# Power_MPU.net
KiCad netlist of a schematic drawn in Altium Designer
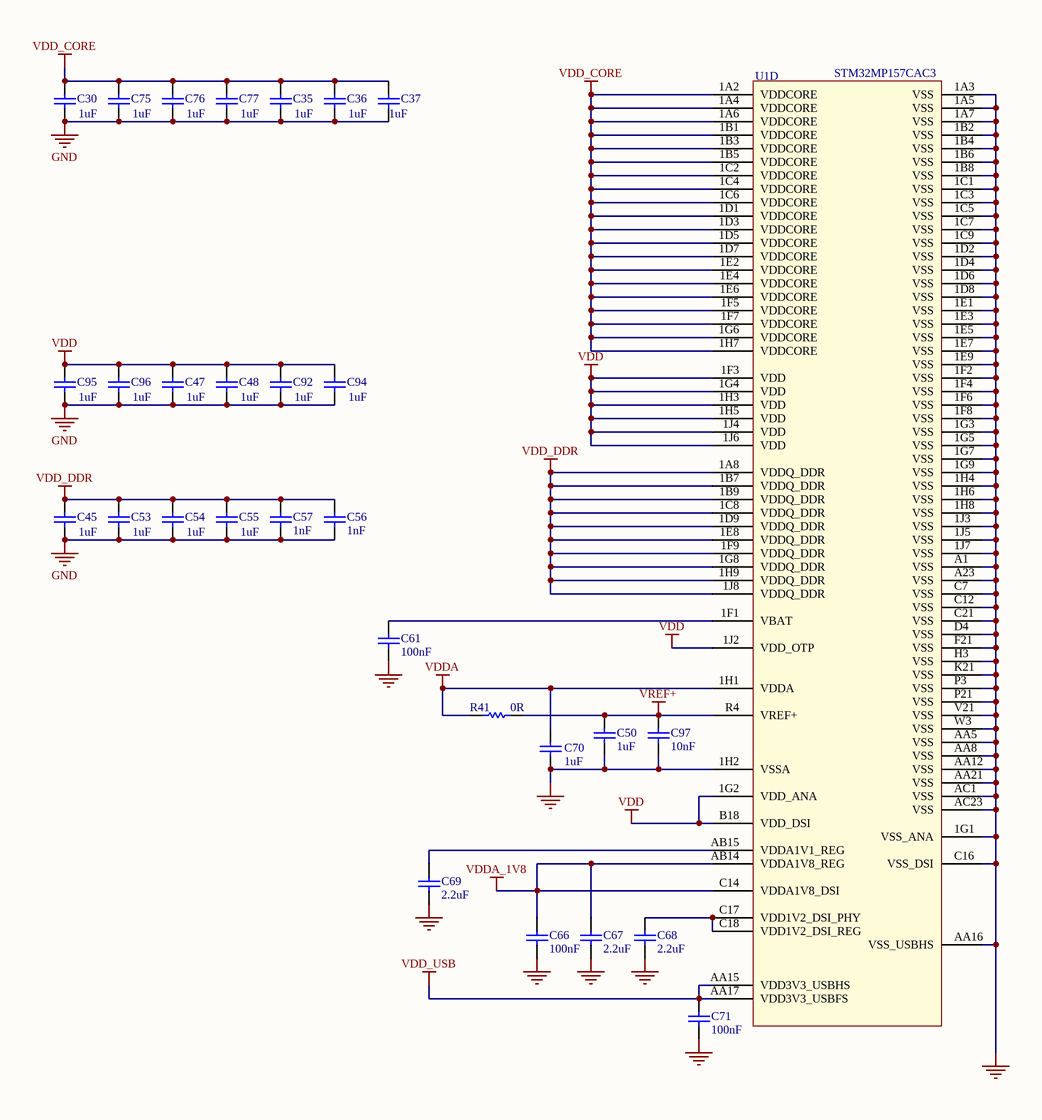
[diagram p0: Power_MPU.SchDoc]

(export (version "E")
  (design (tool "Eeschema 10.0.6"))
  (components
    (comp (ref "C30")
      (value "1uF")
      (footprint "C0402")
      (description "Capacitor, MLCC, 1uF, 25V, X5R, 10%, 0402, T=0,5mm")
      (fields
        (field (name "INTERNAL_PART_NUMBER") "MCD-00095")
        (field (name "MANUFACTURER_PART_NUMBER") "GRM155R61E105KA12")
        (field (name "PROVIDED_BY") "SUBCO")
      )
      (libsource (lib "MCD_PARTS_database") (part "Capacitor"))
    )
    (comp (ref "C35")
      (value "1uF")
      (footprint "C0402")
      (description "Capacitor, MLCC, 1uF, 25V, X5R, 10%, 0402, T=0,5mm")
      (fields
        (field (name "INTERNAL_PART_NUMBER") "MCD-00095")
        (field (name "MANUFACTURER_PART_NUMBER") "GRM155R61E105KA12")
        (field (name "PROVIDED_BY") "SUBCO")
      )
      (libsource (lib "MCD_PARTS_database") (part "Capacitor"))
    )
    (comp (ref "C36")
      (value "1uF")
      (footprint "C0402")
      (description "Capacitor, MLCC, 1uF, 25V, X5R, 10%, 0402, T=0,5mm")
      (fields
        (field (name "INTERNAL_PART_NUMBER") "MCD-00095")
        (field (name "MANUFACTURER_PART_NUMBER") "GRM155R61E105KA12")
        (field (name "PROVIDED_BY") "SUBCO")
      )
      (libsource (lib "MCD_PARTS_database") (part "Capacitor"))
    )
    (comp (ref "C37")
      (value "1uF")
      (footprint "C0402")
      (description "Capacitor, MLCC, 1uF, 25V, X5R, 10%, 0402, T=0,5mm")
      (fields
        (field (name "INTERNAL_PART_NUMBER") "MCD-00095")
        (field (name "MANUFACTURER_PART_NUMBER") "GRM155R61E105KA12")
        (field (name "PROVIDED_BY") "SUBCO")
      )
      (libsource (lib "MCD_PARTS_database") (part "Capacitor"))
    )
    (comp (ref "C45")
      (value "1uF")
      (footprint "C0402")
      (description "Capacitor, MLCC, 1uF, 25V, X5R, 10%, 0402, T=0,5mm")
      (fields
        (field (name "INTERNAL_PART_NUMBER") "MCD-00095")
        (field (name "MANUFACTURER_PART_NUMBER") "GRM155R61E105KA12")
        (field (name "PROVIDED_BY") "SUBCO")
      )
      (libsource (lib "MCD_PARTS_database") (part "Capacitor"))
    )
    (comp (ref "C47")
      (value "1uF")
      (footprint "C0402")
      (description "Capacitor, MLCC, 1uF, 25V, X5R, 10%, 0402, T=0,5mm")
      (fields
        (field (name "INTERNAL_PART_NUMBER") "MCD-00095")
        (field (name "MANUFACTURER_PART_NUMBER") "GRM155R61E105KA12")
        (field (name "PROVIDED_BY") "SUBCO")
      )
      (libsource (lib "MCD_PARTS_database") (part "Capacitor"))
    )
    (comp (ref "C48")
      (value "1uF")
      (footprint "C0402")
      (description "Capacitor, MLCC, 1uF, 25V, X5R, 10%, 0402, T=0,5mm")
      (fields
        (field (name "INTERNAL_PART_NUMBER") "MCD-00095")
        (field (name "MANUFACTURER_PART_NUMBER") "GRM155R61E105KA12")
        (field (name "PROVIDED_BY") "SUBCO")
      )
      (libsource (lib "MCD_PARTS_database") (part "Capacitor"))
    )
    (comp (ref "C50")
      (value "1uF")
      (footprint "C0402")
      (description "Capacitor, MLCC, 1uF, 25V, X5R, 10%, 0402, T=0,5mm")
      (fields
        (field (name "INTERNAL_PART_NUMBER") "MCD-00095")
        (field (name "MANUFACTURER_PART_NUMBER") "GRM155R61E105KA12")
        (field (name "PROVIDED_BY") "SUBCO")
      )
      (libsource (lib "MCD_PARTS_database") (part "Capacitor"))
    )
    (comp (ref "C53")
      (value "1uF")
      (footprint "C0402")
      (description "Capacitor, MLCC, 1uF, 25V, X5R, 10%, 0402, T=0,5mm")
      (fields
        (field (name "INTERNAL_PART_NUMBER") "MCD-00095")
        (field (name "MANUFACTURER_PART_NUMBER") "GRM155R61E105KA12")
        (field (name "PROVIDED_BY") "SUBCO")
      )
      (libsource (lib "MCD_PARTS_database") (part "Capacitor"))
    )
    (comp (ref "C54")
      (value "1uF")
      (footprint "C0402")
      (description "Capacitor, MLCC, 1uF, 25V, X5R, 10%, 0402, T=0,5mm")
      (fields
        (field (name "INTERNAL_PART_NUMBER") "MCD-00095")
        (field (name "MANUFACTURER_PART_NUMBER") "GRM155R61E105KA12")
        (field (name "PROVIDED_BY") "SUBCO")
      )
      (libsource (lib "MCD_PARTS_database") (part "Capacitor"))
    )
    (comp (ref "C55")
      (value "1uF")
      (footprint "C0402")
      (description "Capacitor, MLCC, 1uF, 25V, X5R, 10%, 0402, T=0,5mm")
      (fields
        (field (name "INTERNAL_PART_NUMBER") "MCD-00095")
        (field (name "MANUFACTURER_PART_NUMBER") "GRM155R61E105KA12")
        (field (name "PROVIDED_BY") "SUBCO")
      )
      (libsource (lib "MCD_PARTS_database") (part "Capacitor"))
    )
    (comp (ref "C56")
      (value "1nF")
      (footprint "C0402")
      (description "Capacitor, MLCC, 1nF, 16V, X7R, 10%, 0402, T=0.5mm")
      (fields
        (field (name "INTERNAL_PART_NUMBER") "MCD-00198")
        (field (name "MANUFACTURER_PART_NUMBER") "CC0402KRX7R7BB102")
        (field (name "PROVIDED_BY") "SUBCO")
      )
      (libsource (lib "MCD_PARTS_database") (part "Capacitor"))
    )
    (comp (ref "C57")
      (value "1nF")
      (footprint "C0402")
      (description "Capacitor, MLCC, 1nF, 16V, X7R, 10%, 0402, T=0.5mm")
      (fields
        (field (name "INTERNAL_PART_NUMBER") "MCD-00198")
        (field (name "MANUFACTURER_PART_NUMBER") "CC0402KRX7R7BB102")
        (field (name "PROVIDED_BY") "SUBCO")
      )
      (libsource (lib "MCD_PARTS_database") (part "Capacitor"))
    )
    (comp (ref "C61")
      (value "100nF")
      (footprint "C0402")
      (description "Capacitor, MLCC, 100nF, 16V, X7R, 10%, 0402, T=0.5mm")
      (fields
        (field (name "INTERNAL_PART_NUMBER") "MCD-00006")
        (field (name "MANUFACTURER_PART_NUMBER") "CC0402KRX7R7BB104")
        (field (name "PROVIDED_BY") "SUBCO")
      )
      (libsource (lib "MCD_PARTS_database") (part "Capacitor"))
    )
    (comp (ref "C66")
      (value "100nF")
      (footprint "C0402")
      (description "Capacitor, MLCC, 100nF, 16V, X7R, 10%, 0402, T=0.5mm")
      (fields
        (field (name "INTERNAL_PART_NUMBER") "MCD-00006")
        (field (name "MANUFACTURER_PART_NUMBER") "CC0402KRX7R7BB104")
        (field (name "PROVIDED_BY") "SUBCO")
      )
      (libsource (lib "MCD_PARTS_database") (part "Capacitor"))
    )
    (comp (ref "C67")
      (value "2.2uF")
      (footprint "C0402")
      (description "Capacitor,MLCC,2.2uF,6V3,X5R,10%,0402,T=0.5")
      (fields
        (field (name "INTERNAL_PART_NUMBER") "MCD-01823")
        (field (name "MANUFACTURER_PART_NUMBER") "GRM155R60J225KE95D")
        (field (name "PROVIDED_BY") "SUBCO")
      )
      (libsource (lib "MCD_PARTS_database") (part "Capacitor"))
    )
    (comp (ref "C68")
      (value "2.2uF")
      (footprint "C0402")
      (description "Capacitor,MLCC,2.2uF,6V3,X5R,10%,0402,T=0.5")
      (fields
        (field (name "INTERNAL_PART_NUMBER") "MCD-01823")
        (field (name "MANUFACTURER_PART_NUMBER") "GRM155R60J225KE95D")
        (field (name "PROVIDED_BY") "SUBCO")
      )
      (libsource (lib "MCD_PARTS_database") (part "Capacitor"))
    )
    (comp (ref "C69")
      (value "2.2uF")
      (footprint "C0402")
      (description "Capacitor,MLCC,2.2uF,6V3,X5R,10%,0402,T=0.5")
      (fields
        (field (name "INTERNAL_PART_NUMBER") "MCD-01823")
        (field (name "MANUFACTURER_PART_NUMBER") "GRM155R60J225KE95D")
        (field (name "PROVIDED_BY") "SUBCO")
      )
      (libsource (lib "MCD_PARTS_database") (part "Capacitor"))
    )
    (comp (ref "C70")
      (value "1uF")
      (footprint "C0402")
      (description "Capacitor, MLCC, 1uF, 25V, X5R, 10%, 0402, T=0,5mm")
      (fields
        (field (name "INTERNAL_PART_NUMBER") "MCD-00095")
        (field (name "MANUFACTURER_PART_NUMBER") "GRM155R61E105KA12")
        (field (name "PROVIDED_BY") "SUBCO")
      )
      (libsource (lib "MCD_PARTS_database") (part "Capacitor"))
    )
    (comp (ref "C71")
      (value "100nF")
      (footprint "C0402")
      (description "Capacitor, MLCC, 100nF, 16V, X7R, 10%, 0402, T=0.5mm")
      (fields
        (field (name "INTERNAL_PART_NUMBER") "MCD-00006")
        (field (name "MANUFACTURER_PART_NUMBER") "CC0402KRX7R7BB104")
        (field (name "PROVIDED_BY") "SUBCO")
      )
      (libsource (lib "MCD_PARTS_database") (part "Capacitor"))
    )
    (comp (ref "C75")
      (value "1uF")
      (footprint "C0402")
      (description "Capacitor, MLCC, 1uF, 25V, X5R, 10%, 0402, T=0,5mm")
      (fields
        (field (name "INTERNAL_PART_NUMBER") "MCD-00095")
        (field (name "MANUFACTURER_PART_NUMBER") "GRM155R61E105KA12")
        (field (name "PROVIDED_BY") "SUBCO")
      )
      (libsource (lib "MCD_PARTS_database") (part "Capacitor"))
    )
    (comp (ref "C76")
      (value "1uF")
      (footprint "C0402")
      (description "Capacitor, MLCC, 1uF, 25V, X5R, 10%, 0402, T=0,5mm")
      (fields
        (field (name "INTERNAL_PART_NUMBER") "MCD-00095")
        (field (name "MANUFACTURER_PART_NUMBER") "GRM155R61E105KA12")
        (field (name "PROVIDED_BY") "SUBCO")
      )
      (libsource (lib "MCD_PARTS_database") (part "Capacitor"))
    )
    (comp (ref "C77")
      (value "1uF")
      (footprint "C0402")
      (description "Capacitor, MLCC, 1uF, 25V, X5R, 10%, 0402, T=0,5mm")
      (fields
        (field (name "INTERNAL_PART_NUMBER") "MCD-00095")
        (field (name "MANUFACTURER_PART_NUMBER") "GRM155R61E105KA12")
        (field (name "PROVIDED_BY") "SUBCO")
      )
      (libsource (lib "MCD_PARTS_database") (part "Capacitor"))
    )
    (comp (ref "C92")
      (value "1uF")
      (footprint "C0402")
      (description "Capacitor, MLCC, 1uF, 25V, X5R, 10%, 0402, T=0,5mm")
      (fields
        (field (name "INTERNAL_PART_NUMBER") "MCD-00095")
        (field (name "MANUFACTURER_PART_NUMBER") "GRM155R61E105KA12")
        (field (name "PROVIDED_BY") "SUBCO")
      )
      (libsource (lib "MCD_PARTS_database") (part "Capacitor"))
    )
    (comp (ref "C94")
      (value "1uF")
      (footprint "C0402")
      (description "Capacitor, MLCC, 1uF, 25V, X5R, 10%, 0402, T=0,5mm")
      (fields
        (field (name "INTERNAL_PART_NUMBER") "MCD-00095")
        (field (name "MANUFACTURER_PART_NUMBER") "GRM155R61E105KA12")
        (field (name "PROVIDED_BY") "SUBCO")
      )
      (libsource (lib "MCD_PARTS_database") (part "Capacitor"))
    )
    (comp (ref "C95")
      (value "1uF")
      (footprint "C0402")
      (description "Capacitor, MLCC, 1uF, 25V, X5R, 10%, 0402, T=0,5mm")
      (fields
        (field (name "INTERNAL_PART_NUMBER") "MCD-00095")
        (field (name "MANUFACTURER_PART_NUMBER") "GRM155R61E105KA12")
        (field (name "PROVIDED_BY") "SUBCO")
      )
      (libsource (lib "MCD_PARTS_database") (part "Capacitor"))
    )
    (comp (ref "C96")
      (value "1uF")
      (footprint "C0402")
      (description "Capacitor, MLCC, 1uF, 25V, X5R, 10%, 0402, T=0,5mm")
      (fields
        (field (name "INTERNAL_PART_NUMBER") "MCD-00095")
        (field (name "MANUFACTURER_PART_NUMBER") "GRM155R61E105KA12")
        (field (name "PROVIDED_BY") "SUBCO")
      )
      (libsource (lib "MCD_PARTS_database") (part "Capacitor"))
    )
    (comp (ref "C97")
      (value "10nF")
      (footprint "C0402")
      (description "Capacitor, MLCC, 10nF, 16V, X7R, 10%, 0402, T=0.5mm")
      (fields
        (field (name "INTERNAL_PART_NUMBER") "MCD-00011")
        (field (name "MANUFACTURER_PART_NUMBER") "CC0402KRX7R7BB103")
        (field (name "PROVIDED_BY") "SUBCO")
      )
      (libsource (lib "MCD_PARTS_database") (part "Capacitor"))
    )
    (comp (ref "R41")
      (value "0R")
      (footprint "R0402")
      (description "Resistor,0R,0402,5%,1/16W")
      (fields
        (field (name "INTERNAL_PART_NUMBER") "MCD-00052")
        (field (name "MANUFACTURER_PART_NUMBER") "RC0402JR-070RL")
        (field (name "PROVIDED_BY") "SUBCO")
      )
      (libsource (lib "MCD_PARTS_database") (part "Resistor"))
    )
    (comp (ref "U1")
      (value "STM32MP157CAC3")
      (footprint "ICC_TFBGA361_12X12_STM32MP157CAC3_P050-065")
      (description "MPU TFBGA12x12 secure boot+crypto")
      (fields
        (field (name "INTERNAL_PART_NUMBER") "MCD-00677")
        (field (name "MANUFACTURER") "STMICROELECTRONICS")
        (field (name "PROVIDED_BY") "SUBCO with ST control")
      )
      (libsource (lib "MCD_PARTS_database") (part "STM32MP157CAC3"))
    )
  )
  (nets
    (net (code "1") (name "GND") (class "Default")
      (node (ref "C30") (pin "1") (pinfunction "1_1") (pintype "passive"))
      (node (ref "C35") (pin "1") (pinfunction "1_1") (pintype "passive"))
      (node (ref "C36") (pin "1") (pinfunction "1_1") (pintype "passive"))
      (node (ref "C37") (pin "1") (pinfunction "1_1") (pintype "passive"))
      (node (ref "C45") (pin "1") (pinfunction "1_1") (pintype "passive"))
      (node (ref "C47") (pin "1") (pinfunction "1_1") (pintype "passive"))
      (node (ref "C48") (pin "1") (pinfunction "1_1") (pintype "passive"))
      (node (ref "C50") (pin "1") (pinfunction "1_1") (pintype "passive"))
      (node (ref "C53") (pin "1") (pinfunction "1_1") (pintype "passive"))
      (node (ref "C54") (pin "1") (pinfunction "1_1") (pintype "passive"))
      (node (ref "C55") (pin "1") (pinfunction "1_1") (pintype "passive"))
      (node (ref "C56") (pin "1") (pinfunction "1_1") (pintype "passive"))
      (node (ref "C57") (pin "1") (pinfunction "1_1") (pintype "passive"))
      (node (ref "C61") (pin "1") (pinfunction "1_1") (pintype "passive"))
      (node (ref "C66") (pin "1") (pinfunction "1_1") (pintype "passive"))
      (node (ref "C67") (pin "1") (pinfunction "1_1") (pintype "passive"))
      (node (ref "C68") (pin "1") (pinfunction "1_1") (pintype "passive"))
      (node (ref "C69") (pin "1") (pinfunction "1_1") (pintype "passive"))
      (node (ref "C70") (pin "1") (pinfunction "1_1") (pintype "passive"))
      (node (ref "C71") (pin "1") (pinfunction "1_1") (pintype "passive"))
      (node (ref "C75") (pin "1") (pinfunction "1_1") (pintype "passive"))
      (node (ref "C76") (pin "1") (pinfunction "1_1") (pintype "passive"))
      (node (ref "C77") (pin "1") (pinfunction "1_1") (pintype "passive"))
      (node (ref "C92") (pin "1") (pinfunction "1_1") (pintype "passive"))
      (node (ref "C94") (pin "1") (pinfunction "1_1") (pintype "passive"))
      (node (ref "C95") (pin "1") (pinfunction "1_1") (pintype "passive"))
      (node (ref "C96") (pin "1") (pinfunction "1_1") (pintype "passive"))
      (node (ref "C97") (pin "1") (pinfunction "1_1") (pintype "passive"))
      (node (ref "U1") (pin "1A3") (pinfunction "VSS_1A3") (pintype "passive"))
      (node (ref "U1") (pin "1A5") (pinfunction "VSS_1A5") (pintype "passive"))
      (node (ref "U1") (pin "1A7") (pinfunction "VSS_1A7") (pintype "passive"))
      (node (ref "U1") (pin "1B2") (pinfunction "VSS_1B2") (pintype "passive"))
      (node (ref "U1") (pin "1B4") (pinfunction "VSS_1B4") (pintype "passive"))
      (node (ref "U1") (pin "1B6") (pinfunction "VSS_1B6") (pintype "passive"))
      (node (ref "U1") (pin "1B8") (pinfunction "VSS_1B8") (pintype "passive"))
      (node (ref "U1") (pin "1C1") (pinfunction "VSS_1C1") (pintype "passive"))
      (node (ref "U1") (pin "1C3") (pinfunction "VSS_1C3") (pintype "passive"))
      (node (ref "U1") (pin "1C5") (pinfunction "VSS_1C5") (pintype "passive"))
      (node (ref "U1") (pin "1C7") (pinfunction "VSS_1C7") (pintype "passive"))
      (node (ref "U1") (pin "1C9") (pinfunction "VSS_1C9") (pintype "passive"))
      (node (ref "U1") (pin "1D2") (pinfunction "VSS_1D2") (pintype "passive"))
      (node (ref "U1") (pin "1D4") (pinfunction "VSS_1D4") (pintype "passive"))
      (node (ref "U1") (pin "1D6") (pinfunction "VSS_1D6") (pintype "passive"))
      (node (ref "U1") (pin "1D8") (pinfunction "VSS_1D8") (pintype "passive"))
      (node (ref "U1") (pin "1E1") (pinfunction "VSS_1E1") (pintype "passive"))
      (node (ref "U1") (pin "1E3") (pinfunction "VSS_1E3") (pintype "passive"))
      (node (ref "U1") (pin "1E5") (pinfunction "VSS_1E5") (pintype "passive"))
      (node (ref "U1") (pin "1E7") (pinfunction "VSS_1E7") (pintype "passive"))
      (node (ref "U1") (pin "1E9") (pinfunction "VSS_1E9") (pintype "passive"))
      (node (ref "U1") (pin "1F2") (pinfunction "VSS_1F2") (pintype "passive"))
      (node (ref "U1") (pin "1F4") (pinfunction "VSS_1F4") (pintype "passive"))
      (node (ref "U1") (pin "1F6") (pinfunction "VSS_1F6") (pintype "passive"))
      (node (ref "U1") (pin "1F8") (pinfunction "VSS_1F8") (pintype "passive"))
      (node (ref "U1") (pin "1G1") (pinfunction "VSS_ANA_1G1") (pintype "passive"))
      (node (ref "U1") (pin "1G3") (pinfunction "VSS_1G3") (pintype "passive"))
      (node (ref "U1") (pin "1G5") (pinfunction "VSS_1G5") (pintype "passive"))
      (node (ref "U1") (pin "1G7") (pinfunction "VSS_1G7") (pintype "passive"))
      (node (ref "U1") (pin "1G9") (pinfunction "VSS_1G9") (pintype "passive"))
      (node (ref "U1") (pin "1H2") (pinfunction "VSSA_1H2") (pintype "passive"))
      (node (ref "U1") (pin "1H4") (pinfunction "VSS_1H4") (pintype "passive"))
      (node (ref "U1") (pin "1H6") (pinfunction "VSS_1H6") (pintype "passive"))
      (node (ref "U1") (pin "1H8") (pinfunction "VSS_1H8") (pintype "passive"))
      (node (ref "U1") (pin "1J3") (pinfunction "VSS_1J3") (pintype "passive"))
      (node (ref "U1") (pin "1J5") (pinfunction "VSS_1J5") (pintype "passive"))
      (node (ref "U1") (pin "1J7") (pinfunction "VSS_1J7") (pintype "passive"))
      (node (ref "U1") (pin "A1") (pinfunction "VSS_A1") (pintype "passive"))
      (node (ref "U1") (pin "A23") (pinfunction "VSS_A23") (pintype "passive"))
      (node (ref "U1") (pin "AA12") (pinfunction "VSS_AA12") (pintype "passive"))
      (node (ref "U1") (pin "AA16") (pinfunction "VSS_USBHS_AA16") (pintype "passive"))
      (node (ref "U1") (pin "AA21") (pinfunction "VSS_AA21") (pintype "passive"))
      (node (ref "U1") (pin "AA5") (pinfunction "VSS_AA5") (pintype "passive"))
      (node (ref "U1") (pin "AA8") (pinfunction "VSS_AA8") (pintype "passive"))
      (node (ref "U1") (pin "AC1") (pinfunction "VSS_AC1") (pintype "passive"))
      (node (ref "U1") (pin "AC23") (pinfunction "VSS_AC23") (pintype "passive"))
      (node (ref "U1") (pin "C12") (pinfunction "VSS_C12") (pintype "passive"))
      (node (ref "U1") (pin "C16") (pinfunction "VSS_DSI_C16") (pintype "passive"))
      (node (ref "U1") (pin "C21") (pinfunction "VSS_C21") (pintype "passive"))
      (node (ref "U1") (pin "C7") (pinfunction "VSS_C7") (pintype "passive"))
      (node (ref "U1") (pin "D4") (pinfunction "VSS_D4") (pintype "passive"))
      (node (ref "U1") (pin "F21") (pinfunction "VSS_F21") (pintype "passive"))
      (node (ref "U1") (pin "H3") (pinfunction "VSS_H3") (pintype "passive"))
      (node (ref "U1") (pin "K21") (pinfunction "VSS_K21") (pintype "passive"))
      (node (ref "U1") (pin "P21") (pinfunction "VSS_P21") (pintype "passive"))
      (node (ref "U1") (pin "P3") (pinfunction "VSS_P3") (pintype "passive"))
      (node (ref "U1") (pin "V21") (pinfunction "VSS_V21") (pintype "passive"))
      (node (ref "U1") (pin "W3") (pinfunction "VSS_W3") (pintype "passive"))
    )
    (net (code "2") (name "Net-(U1D-VBAT)") (class "Default")
      (node (ref "C61") (pin "2") (pinfunction "2_2") (pintype "passive"))
      (node (ref "U1") (pin "1F1") (pinfunction "VBAT_1F1") (pintype "passive"))
    )
    (net (code "3") (name "Net-(U1D-VDD1V2_DSI_PHY)") (class "Default")
      (node (ref "C68") (pin "2") (pinfunction "2_2") (pintype "passive"))
      (node (ref "U1") (pin "C17") (pinfunction "VDD1V2_DSI_PHY_C17") (pintype "passive"))
      (node (ref "U1") (pin "C18") (pinfunction "VDD1V2_DSI_REG_C18") (pintype "passive"))
    )
    (net (code "4") (name "Net-(U1D-VDDA1V1_REG)") (class "Default")
      (node (ref "C69") (pin "2") (pinfunction "2_2") (pintype "passive"))
      (node (ref "U1") (pin "AB15") (pinfunction "VDDA1V1_REG_AB15") (pintype "passive"))
    )
    (net (code "5") (name "VDD") (class "Default")
      (node (ref "C47") (pin "2") (pinfunction "2_2") (pintype "passive"))
      (node (ref "C48") (pin "2") (pinfunction "2_2") (pintype "passive"))
      (node (ref "C92") (pin "2") (pinfunction "2_2") (pintype "passive"))
      (node (ref "C94") (pin "2") (pinfunction "2_2") (pintype "passive"))
      (node (ref "C95") (pin "2") (pinfunction "2_2") (pintype "passive"))
      (node (ref "C96") (pin "2") (pinfunction "2_2") (pintype "passive"))
      (node (ref "U1") (pin "1F3") (pinfunction "VDD_1F3") (pintype "passive"))
      (node (ref "U1") (pin "1G2") (pinfunction "VDD_ANA_1G2") (pintype "passive"))
      (node (ref "U1") (pin "1G4") (pinfunction "VDD_1G4") (pintype "passive"))
      (node (ref "U1") (pin "1H3") (pinfunction "VDD_1H3") (pintype "passive"))
      (node (ref "U1") (pin "1H5") (pinfunction "VDD_1H5") (pintype "passive"))
      (node (ref "U1") (pin "1J2") (pinfunction "VDD_OTP_1J2") (pintype "passive"))
      (node (ref "U1") (pin "1J4") (pinfunction "VDD_1J4") (pintype "passive"))
      (node (ref "U1") (pin "1J6") (pinfunction "VDD_1J6") (pintype "passive"))
      (node (ref "U1") (pin "B18") (pinfunction "VDD_DSI_B18") (pintype "passive"))
    )
    (net (code "6") (name "VDDA") (class "Default")
      (node (ref "C70") (pin "2") (pinfunction "2_2") (pintype "passive"))
      (node (ref "R41") (pin "1") (pinfunction "1_1") (pintype "passive"))
      (node (ref "U1") (pin "1H1") (pinfunction "VDDA_1H1") (pintype "passive"))
    )
    (net (code "7") (name "VDDA_1V8") (class "Default")
      (node (ref "C66") (pin "2") (pinfunction "2_2") (pintype "passive"))
      (node (ref "C67") (pin "2") (pinfunction "2_2") (pintype "passive"))
      (node (ref "U1") (pin "AB14") (pinfunction "VDDA1V8_REG_AB14") (pintype "passive"))
      (node (ref "U1") (pin "C14") (pinfunction "VDDA1V8_DSI_C14") (pintype "passive"))
    )
    (net (code "8") (name "VDD_CORE") (class "Default")
      (node (ref "C30") (pin "2") (pinfunction "2_2") (pintype "passive"))
      (node (ref "C35") (pin "2") (pinfunction "2_2") (pintype "passive"))
      (node (ref "C36") (pin "2") (pinfunction "2_2") (pintype "passive"))
      (node (ref "C37") (pin "2") (pinfunction "2_2") (pintype "passive"))
      (node (ref "C75") (pin "2") (pinfunction "2_2") (pintype "passive"))
      (node (ref "C76") (pin "2") (pinfunction "2_2") (pintype "passive"))
      (node (ref "C77") (pin "2") (pinfunction "2_2") (pintype "passive"))
      (node (ref "U1") (pin "1A2") (pinfunction "VDDCORE_1A2") (pintype "passive"))
      (node (ref "U1") (pin "1A4") (pinfunction "VDDCORE_1A4") (pintype "passive"))
      (node (ref "U1") (pin "1A6") (pinfunction "VDDCORE_1A6") (pintype "passive"))
      (node (ref "U1") (pin "1B1") (pinfunction "VDDCORE_1B1") (pintype "passive"))
      (node (ref "U1") (pin "1B3") (pinfunction "VDDCORE_1B3") (pintype "passive"))
      (node (ref "U1") (pin "1B5") (pinfunction "VDDCORE_1B5") (pintype "passive"))
      (node (ref "U1") (pin "1C2") (pinfunction "VDDCORE_1C2") (pintype "passive"))
      (node (ref "U1") (pin "1C4") (pinfunction "VDDCORE_1C4") (pintype "passive"))
      (node (ref "U1") (pin "1C6") (pinfunction "VDDCORE_1C6") (pintype "passive"))
      (node (ref "U1") (pin "1D1") (pinfunction "VDDCORE_1D1") (pintype "passive"))
      (node (ref "U1") (pin "1D3") (pinfunction "VDDCORE_1D3") (pintype "passive"))
      (node (ref "U1") (pin "1D5") (pinfunction "VDDCORE_1D5") (pintype "passive"))
      (node (ref "U1") (pin "1D7") (pinfunction "VDDCORE_1D7") (pintype "passive"))
      (node (ref "U1") (pin "1E2") (pinfunction "VDDCORE_1E2") (pintype "passive"))
      (node (ref "U1") (pin "1E4") (pinfunction "VDDCORE_1E4") (pintype "passive"))
      (node (ref "U1") (pin "1E6") (pinfunction "VDDCORE_1E6") (pintype "passive"))
      (node (ref "U1") (pin "1F5") (pinfunction "VDDCORE_1F5") (pintype "passive"))
      (node (ref "U1") (pin "1F7") (pinfunction "VDDCORE_1F7") (pintype "passive"))
      (node (ref "U1") (pin "1G6") (pinfunction "VDDCORE_1G6") (pintype "passive"))
      (node (ref "U1") (pin "1H7") (pinfunction "VDDCORE_1H7") (pintype "passive"))
    )
    (net (code "9") (name "VDD_DDR") (class "Default")
      (node (ref "C45") (pin "2") (pinfunction "2_2") (pintype "passive"))
      (node (ref "C53") (pin "2") (pinfunction "2_2") (pintype "passive"))
      (node (ref "C54") (pin "2") (pinfunction "2_2") (pintype "passive"))
      (node (ref "C55") (pin "2") (pinfunction "2_2") (pintype "passive"))
      (node (ref "C56") (pin "2") (pinfunction "2_2") (pintype "passive"))
      (node (ref "C57") (pin "2") (pinfunction "2_2") (pintype "passive"))
      (node (ref "U1") (pin "1A8") (pinfunction "VDDQ_DDR_1A8") (pintype "passive"))
      (node (ref "U1") (pin "1B7") (pinfunction "VDDQ_DDR_1B7") (pintype "passive"))
      (node (ref "U1") (pin "1B9") (pinfunction "VDDQ_DDR_1B9") (pintype "passive"))
      (node (ref "U1") (pin "1C8") (pinfunction "VDDQ_DDR_1C8") (pintype "passive"))
      (node (ref "U1") (pin "1D9") (pinfunction "VDDQ_DDR_1D9") (pintype "passive"))
      (node (ref "U1") (pin "1E8") (pinfunction "VDDQ_DDR_1E8") (pintype "passive"))
      (node (ref "U1") (pin "1F9") (pinfunction "VDDQ_DDR_1F9") (pintype "passive"))
      (node (ref "U1") (pin "1G8") (pinfunction "VDDQ_DDR_1G8") (pintype "passive"))
      (node (ref "U1") (pin "1H9") (pinfunction "VDDQ_DDR_1H9") (pintype "passive"))
      (node (ref "U1") (pin "1J8") (pinfunction "VDDQ_DDR_1J8") (pintype "passive"))
    )
    (net (code "10") (name "VDD_USB") (class "Default")
      (node (ref "C71") (pin "2") (pinfunction "2_2") (pintype "passive"))
      (node (ref "U1") (pin "AA15") (pinfunction "VDD3V3_USBHS_AA15") (pintype "passive"))
      (node (ref "U1") (pin "AA17") (pinfunction "VDD3V3_USBFS_AA17") (pintype "passive"))
    )
    (net (code "11") (name "VREF+") (class "Default")
      (node (ref "C50") (pin "2") (pinfunction "2_2") (pintype "passive"))
      (node (ref "C97") (pin "2") (pinfunction "2_2") (pintype "passive"))
      (node (ref "R41") (pin "2") (pinfunction "2_2") (pintype "passive"))
      (node (ref "U1") (pin "R4") (pinfunction "VREF+_R4") (pintype "passive"))
    )
  )
)
